# SCH_IRRemote.net
KiCad netlist of a schematic drawn in EasyEDA
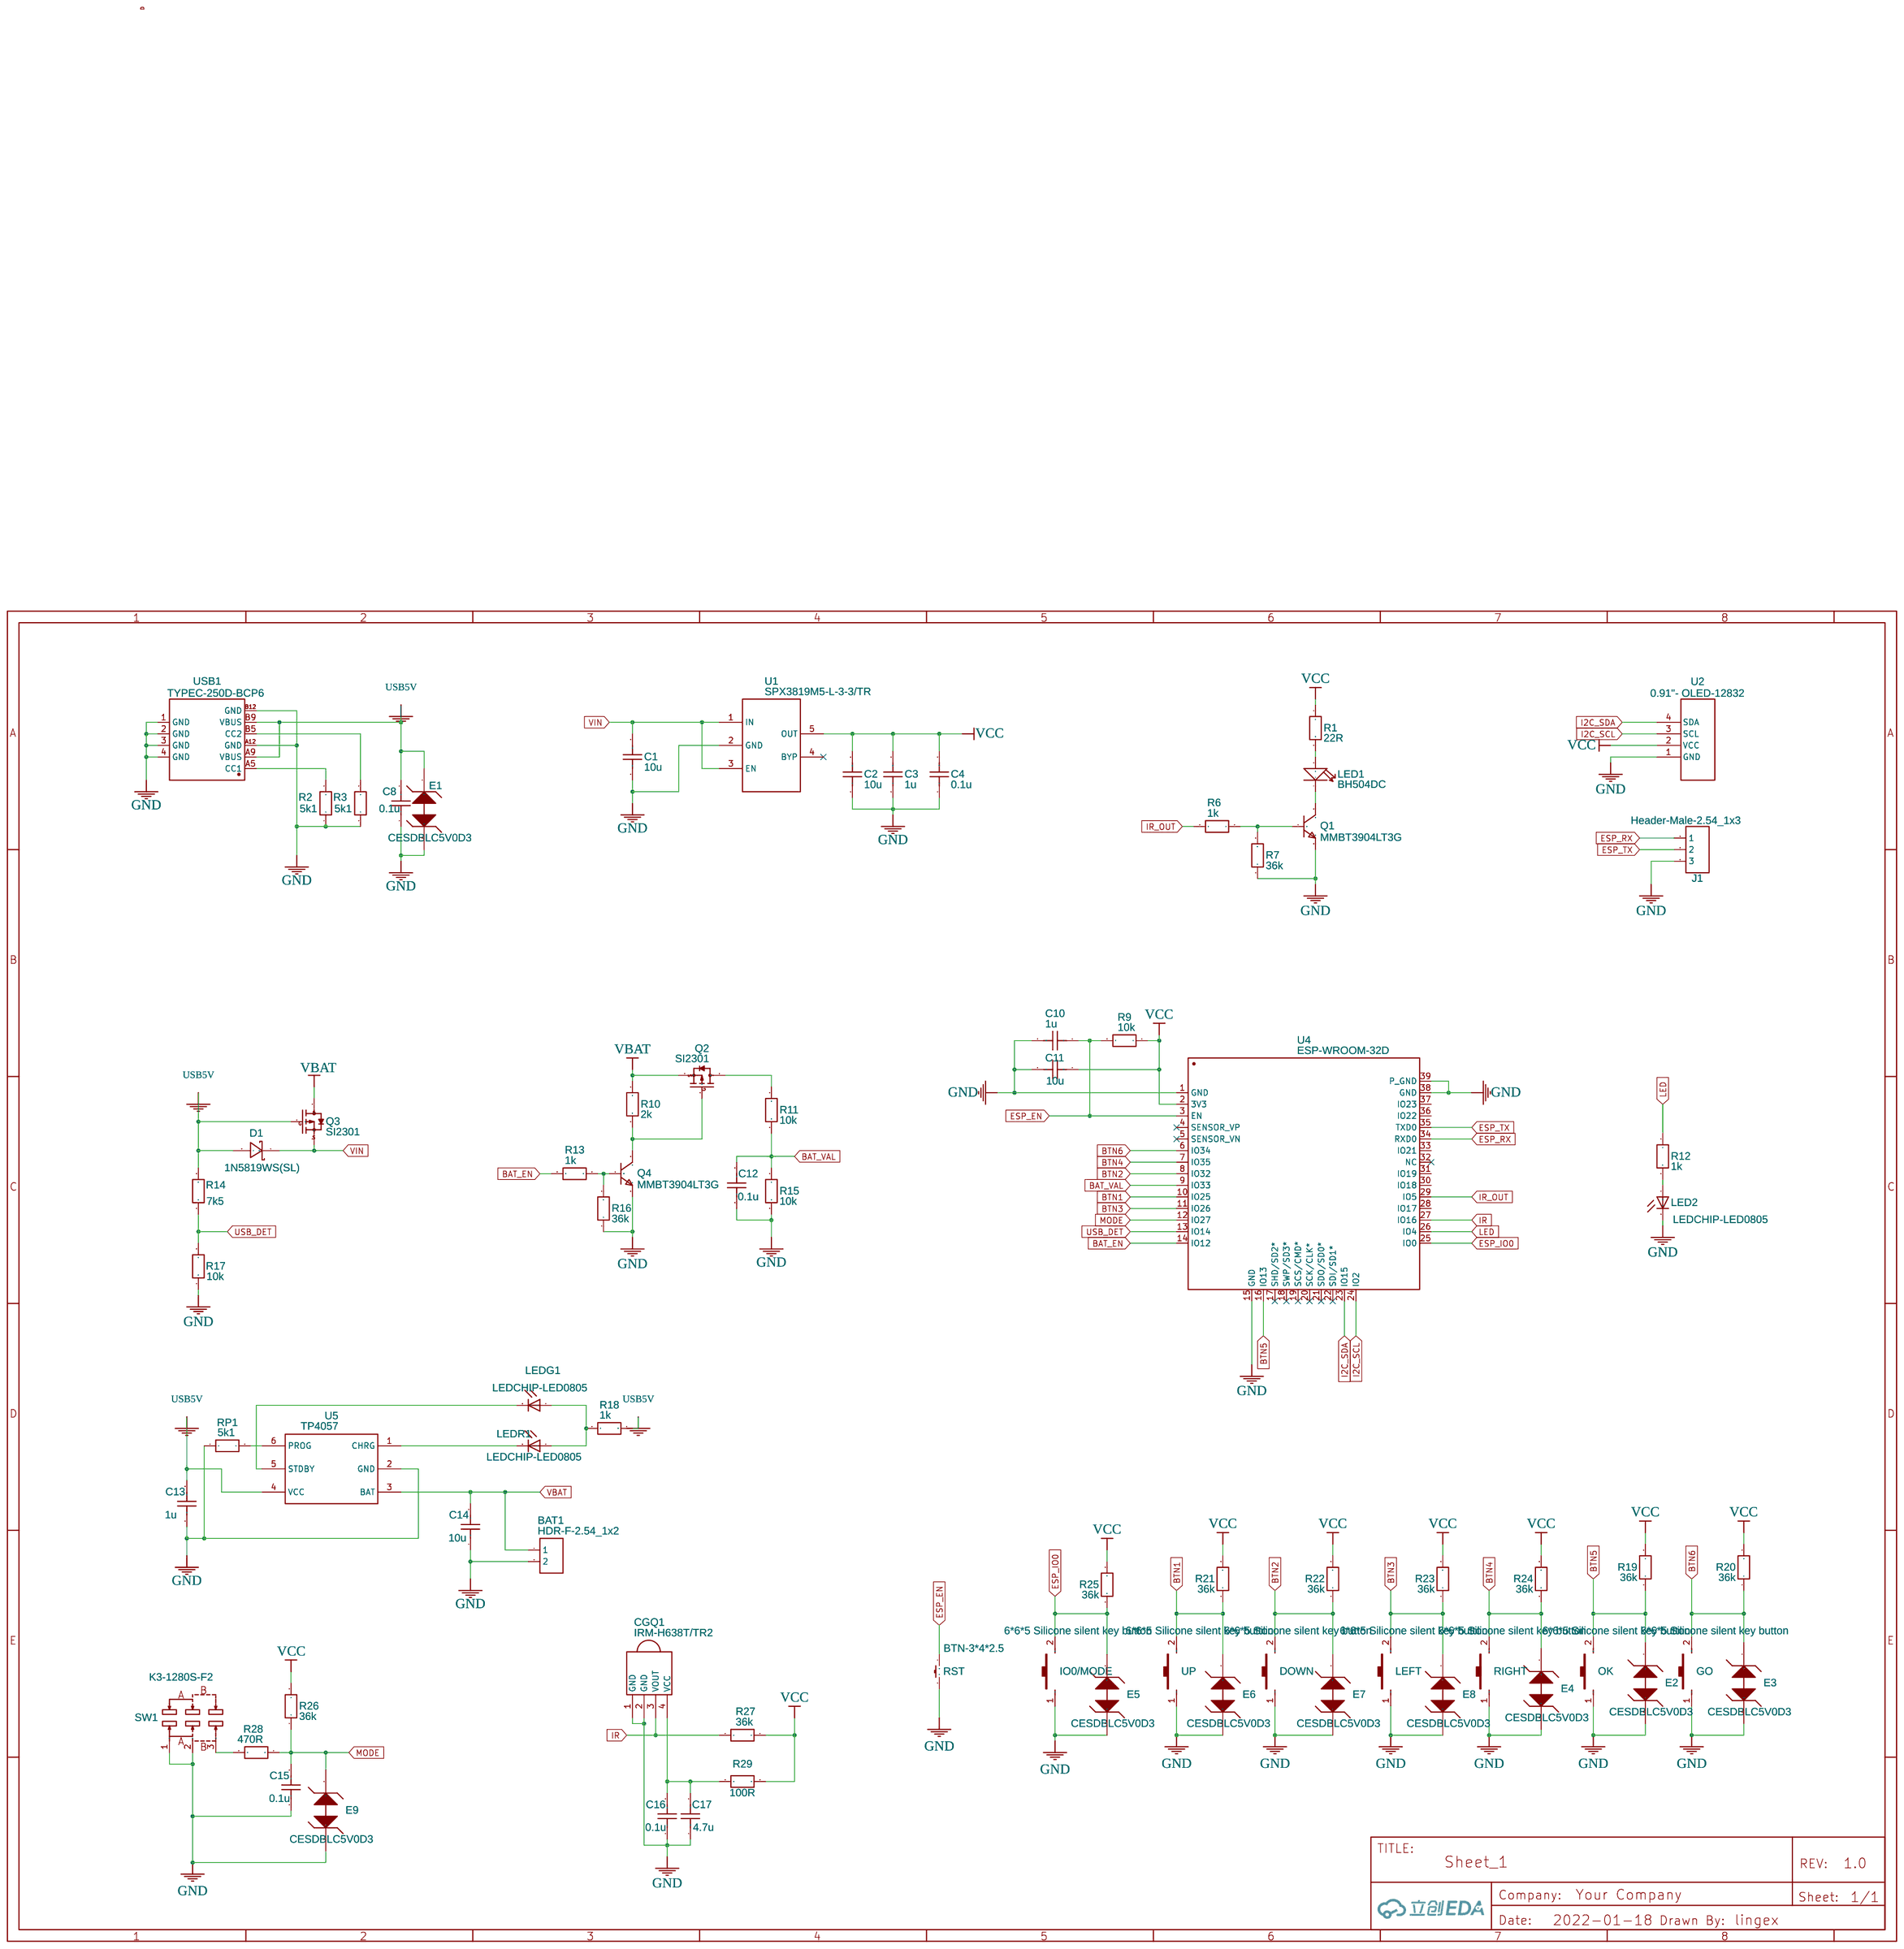
[diagram p0: schematic sheet]

(export (version "E")
  (design (tool "Eeschema 10.0.6"))
  (components
    (comp (ref "BAT1")
      (value "HDR-F-2.54_1x2")
      (fields (field (name "BOM_Supplier Part") "C49661"))
      (libsource (lib "") (part "HDR-F-2.54_1x2"))
    )
    (comp (ref "C1") (value "10u") (libsource (lib "") (part "C_0603_US")))
    (comp (ref "C2") (value "10u") (libsource (lib "") (part "C_0603_US")))
    (comp (ref "C3") (value "1u") (libsource (lib "") (part "C_0603_US")))
    (comp (ref "C4") (value "0.1u") (libsource (lib "") (part "C_0603_US")))
    (comp (ref "C8") (value "0.1u") (libsource (lib "") (part "C_0603_US")))
    (comp (ref "C10") (value "1u") (libsource (lib "") (part "C_0603_US_2")))
    (comp (ref "C11") (value "10u") (libsource (lib "") (part "C_0603_US_2")))
    (comp (ref "C12") (value "0.1u") (libsource (lib "") (part "C_0603_US_1")))
    (comp (ref "C13") (value "1u") (libsource (lib "") (part "C_0603_US")))
    (comp (ref "C14") (value "10u") (libsource (lib "") (part "C_0603_US")))
    (comp (ref "C15") (value "0.1u") (libsource (lib "") (part "C_0603_US")))
    (comp (ref "C16") (value "0.1u") (libsource (lib "") (part "C_0603_US")))
    (comp (ref "C17") (value "4.7u") (libsource (lib "") (part "C_0603_US")))
    (comp (ref "CGQ1")
      (value "IRM-H638T/TR2")
      (fields (field (name "BOM_Supplier Part") "C91447"))
      (libsource (lib "") (part "IRM-H638T/TR2"))
    )
    (comp (ref "D1")
      (value "1N5819WS(SL)")
      (fields (field (name "BOM_Supplier Part") "C489147"))
      (libsource (lib "") (part "1N5819WS(SL)"))
    )
    (comp (ref "DOWN")
      (value "6*6*5 Silicone silent key button")
      (fields (field (name "BOM_Supplier Part") "C61120"))
      (libsource (lib "") (part "6*6*5 Silicone silent key button"))
    )
    (comp (ref "E1")
      (value "CESDBLC5V0D3")
      (fields (field (name "BOM_Supplier Part") "C47346"))
      (libsource (lib "") (part "CESDBLC5V0D3"))
    )
    (comp (ref "E2")
      (value "CESDBLC5V0D3")
      (fields (field (name "BOM_Supplier Part") "C47346"))
      (libsource (lib "") (part "CESDBLC5V0D3"))
    )
    (comp (ref "E3")
      (value "CESDBLC5V0D3")
      (fields (field (name "BOM_Supplier Part") "C47346"))
      (libsource (lib "") (part "CESDBLC5V0D3"))
    )
    (comp (ref "E4")
      (value "CESDBLC5V0D3")
      (fields (field (name "BOM_Supplier Part") "C47346"))
      (libsource (lib "") (part "CESDBLC5V0D3"))
    )
    (comp (ref "E5")
      (value "CESDBLC5V0D3")
      (fields (field (name "BOM_Supplier Part") "C47346"))
      (libsource (lib "") (part "CESDBLC5V0D3"))
    )
    (comp (ref "E6")
      (value "CESDBLC5V0D3")
      (fields (field (name "BOM_Supplier Part") "C47346"))
      (libsource (lib "") (part "CESDBLC5V0D3"))
    )
    (comp (ref "E7")
      (value "CESDBLC5V0D3")
      (fields (field (name "BOM_Supplier Part") "C47346"))
      (libsource (lib "") (part "CESDBLC5V0D3"))
    )
    (comp (ref "E8")
      (value "CESDBLC5V0D3")
      (fields (field (name "BOM_Supplier Part") "C47346"))
      (libsource (lib "") (part "CESDBLC5V0D3"))
    )
    (comp (ref "E9")
      (value "CESDBLC5V0D3")
      (fields (field (name "BOM_Supplier Part") "C47346"))
      (libsource (lib "") (part "CESDBLC5V0D3"))
    )
    (comp (ref "GO")
      (value "6*6*5 Silicone silent key button")
      (fields (field (name "BOM_Supplier Part") "C61120"))
      (libsource (lib "") (part "6*6*5 Silicone silent key button_3"))
    )
    (comp (ref "IO0/MODE")
      (value "6*6*5 Silicone silent key button")
      (fields (field (name "BOM_Supplier Part") "C61120"))
      (libsource (lib "") (part "6*6*5 Silicone silent key button_6"))
    )
    (comp (ref "J1")
      (value "Header-Male-2.54_1x3")
      (fields
        (field (name "BOM_Manufacturer Part") "Header2.54mm 1*3P")
        (field (name "BOM_Supplier Part") "C49257")
      )
      (libsource (lib "") (part "Header-Male-2.54_1x3"))
    )
    (comp (ref "LED1") (value "BH504DC") (libsource (lib "") (part "BH504DC")))
    (comp (ref "LED2") (value "LEDCHIP-LED0805") (libsource (lib "") (part "LEDCHIP-LED0805_2")))
    (comp (ref "LEDG1") (value "LEDCHIP-LED0805") (libsource (lib "") (part "LEDCHIP-LED0805_1")))
    (comp (ref "LEDR1") (value "LEDCHIP-LED0805") (libsource (lib "") (part "LEDCHIP-LED0805")))
    (comp (ref "LEFT")
      (value "6*6*5 Silicone silent key button")
      (fields (field (name "BOM_Supplier Part") "C61120"))
      (libsource (lib "") (part "6*6*5 Silicone silent key button_2"))
    )
    (comp (ref "OK")
      (value "6*6*5 Silicone silent key button")
      (fields (field (name "BOM_Supplier Part") "C61120"))
      (libsource (lib "") (part "6*6*5 Silicone silent key button_5"))
    )
    (comp (ref "Q1")
      (value "MMBT3904LT3G")
      (fields (field (name "BOM_Supplier Part") "C150052"))
      (libsource (lib "") (part "MMBT3904LT3G"))
    )
    (comp (ref "Q2")
      (value "SI2301")
      (fields (field (name "BOM_Supplier Part") "C181086"))
      (libsource (lib "") (part "SI2301_1"))
    )
    (comp (ref "Q3")
      (value "SI2301")
      (fields (field (name "BOM_Supplier Part") "C181086"))
      (libsource (lib "") (part "SI2301"))
    )
    (comp (ref "Q4")
      (value "MMBT3904LT3G")
      (fields (field (name "BOM_Supplier Part") "C150052"))
      (libsource (lib "") (part "MMBT3904LT3G"))
    )
    (comp (ref "R1") (value "22R") (libsource (lib "") (part "R_0603_EU_1")))
    (comp (ref "R2") (value "5k1") (libsource (lib "") (part "R_0603_EU")))
    (comp (ref "R3") (value "5k1") (libsource (lib "") (part "R_0603_EU")))
    (comp (ref "R6") (value "1k") (libsource (lib "") (part "R_0603_EU_2")))
    (comp (ref "R7") (value "36k") (libsource (lib "") (part "R_0603_EU")))
    (comp (ref "R9") (value "10k") (libsource (lib "") (part "R_0603_EU_2")))
    (comp (ref "R10") (value "2k") (libsource (lib "") (part "R_0603_EU_1")))
    (comp (ref "R11") (value "10k") (libsource (lib "") (part "R_0603_EU_1")))
    (comp (ref "R12") (value "1k") (libsource (lib "") (part "R_0603_EU_1")))
    (comp (ref "R13") (value "1k") (libsource (lib "") (part "R_0603_EU_2")))
    (comp (ref "R14") (value "7k5") (libsource (lib "") (part "R_0603_EU")))
    (comp (ref "R15") (value "10k") (libsource (lib "") (part "R_0603_EU_1")))
    (comp (ref "R16") (value "36k") (libsource (lib "") (part "R_0603_EU")))
    (comp (ref "R17") (value "10k") (libsource (lib "") (part "R_0603_EU")))
    (comp (ref "R18") (value "1k") (libsource (lib "") (part "R_0603_EU_3")))
    (comp (ref "R19") (value "36k") (libsource (lib "") (part "R_0603_EU")))
    (comp (ref "R20") (value "36k") (libsource (lib "") (part "R_0603_EU")))
    (comp (ref "R21") (value "36k") (libsource (lib "") (part "R_0603_EU")))
    (comp (ref "R22") (value "36k") (libsource (lib "") (part "R_0603_EU")))
    (comp (ref "R23") (value "36k") (libsource (lib "") (part "R_0603_EU")))
    (comp (ref "R24") (value "36k") (libsource (lib "") (part "R_0603_EU")))
    (comp (ref "R25") (value "36k") (libsource (lib "") (part "R_0603_EU")))
    (comp (ref "R26") (value "36k") (libsource (lib "") (part "R_0603_EU")))
    (comp (ref "R27") (value "36k") (libsource (lib "") (part "R_0603_EU_3")))
    (comp (ref "R28") (value "470R") (libsource (lib "") (part "R_0603_EU_2")))
    (comp (ref "R29") (value "100R") (libsource (lib "") (part "R_0603_EU_3")))
    (comp (ref "RIGHT")
      (value "6*6*5 Silicone silent key button")
      (fields (field (name "BOM_Supplier Part") "C61120"))
      (libsource (lib "") (part "6*6*5 Silicone silent key button_4"))
    )
    (comp (ref "RP1") (value "5k1") (libsource (lib "") (part "R_0603_EU_4")))
    (comp (ref "RST")
      (value "BTN-3*4*2.5")
      (fields
        (field (name "BOM_Manufacturer Part") "UK-B0267-ZT-SP25Y")
        (field (name "BOM_Supplier Part") "C493284")
      )
      (libsource (lib "") (part "3*4*2.5 贴片椭圆白头按钮开关"))
    )
    (comp (ref "SW1")
      (value "K3-1280S-F2")
      (fields (field (name "BOM_Supplier Part") "C92658"))
      (libsource (lib "") (part "K3-1280S-F2"))
    )
    (comp (ref "U1")
      (value "SPX3819M5-L-3-3/TR")
      (fields (field (name "BOM_Supplier Part") "C9055"))
      (libsource (lib "") (part "SPX3819M5-L-3-3/TR"))
    )
    (comp (ref "U2") (value "0.91\"- OLED-12832") (libsource (lib "") (part "0.91{dblquote}- OLED-12832")))
    (comp (ref "U4")
      (value "ESP-WROOM-32D")
      (fields (field (name "BOM_Supplier Part") "C2894836"))
      (libsource (lib "") (part "ESP-WROOM-32D"))
    )
    (comp (ref "U5")
      (value "TP4057")
      (fields (field (name "BOM_Supplier Part") "C12044"))
      (libsource (lib "") (part "TP4057"))
    )
    (comp (ref "UP")
      (value "6*6*5 Silicone silent key button")
      (fields (field (name "BOM_Supplier Part") "C61120"))
      (libsource (lib "") (part "6*6*5 Silicone silent key button_1"))
    )
    (comp (ref "USB1")
      (value "TYPEC-250D-BCP6")
      (fields (field (name "BOM_Supplier Part") "C720626"))
      (libsource (lib "") (part "TYPEC-250D-BCP6"))
    )
  )
  (nets
    (net (code "1") (name "BAT_EN") (class "Default")
      (node (ref "R13") (pin "2") (pinfunction "2_2") (pintype "unspecified"))
      (node (ref "U4") (pin "14") (pinfunction "IO12_14") (pintype "unspecified"))
    )
    (net (code "2") (name "BAT_VAL") (class "Default")
      (node (ref "C12") (pin "1") (pinfunction "1_1") (pintype "unspecified"))
      (node (ref "R11") (pin "2") (pinfunction "2_2") (pintype "unspecified"))
      (node (ref "R15") (pin "1") (pinfunction "1_1") (pintype "unspecified"))
      (node (ref "U4") (pin "9") (pinfunction "IO33_9") (pintype "unspecified"))
    )
    (net (code "3") (name "BTN1") (class "Default")
      (node (ref "E6") (pin "1") (pinfunction "1_1") (pintype "input"))
      (node (ref "R21") (pin "1") (pinfunction "1_1") (pintype "unspecified"))
      (node (ref "U4") (pin "10") (pinfunction "IO25_10") (pintype "unspecified"))
      (node (ref "UP") (pin "2") (pinfunction "2_2") (pintype "input"))
    )
    (net (code "4") (name "BTN2") (class "Default")
      (node (ref "DOWN") (pin "2") (pinfunction "2_2") (pintype "input"))
      (node (ref "E7") (pin "1") (pinfunction "1_1") (pintype "input"))
      (node (ref "R22") (pin "1") (pinfunction "1_1") (pintype "unspecified"))
      (node (ref "U4") (pin "8") (pinfunction "IO32_8") (pintype "unspecified"))
    )
    (net (code "5") (name "BTN3") (class "Default")
      (node (ref "E8") (pin "1") (pinfunction "1_1") (pintype "input"))
      (node (ref "LEFT") (pin "2") (pinfunction "2_2") (pintype "input"))
      (node (ref "R23") (pin "1") (pinfunction "1_1") (pintype "unspecified"))
      (node (ref "U4") (pin "11") (pinfunction "IO26_11") (pintype "unspecified"))
    )
    (net (code "6") (name "BTN4") (class "Default")
      (node (ref "E4") (pin "1") (pinfunction "1_1") (pintype "input"))
      (node (ref "R24") (pin "1") (pinfunction "1_1") (pintype "unspecified"))
      (node (ref "RIGHT") (pin "2") (pinfunction "2_2") (pintype "input"))
      (node (ref "U4") (pin "7") (pinfunction "IO35_7") (pintype "unspecified"))
    )
    (net (code "7") (name "BTN5") (class "Default")
      (node (ref "E2") (pin "1") (pinfunction "1_1") (pintype "input"))
      (node (ref "OK") (pin "2") (pinfunction "2_2") (pintype "input"))
      (node (ref "R19") (pin "1") (pinfunction "1_1") (pintype "unspecified"))
      (node (ref "U4") (pin "16") (pinfunction "IO13_16") (pintype "unspecified"))
    )
    (net (code "8") (name "BTN6") (class "Default")
      (node (ref "E3") (pin "1") (pinfunction "1_1") (pintype "input"))
      (node (ref "GO") (pin "2") (pinfunction "2_2") (pintype "input"))
      (node (ref "R20") (pin "1") (pinfunction "1_1") (pintype "unspecified"))
      (node (ref "U4") (pin "6") (pinfunction "IO34_6") (pintype "unspecified"))
    )
    (net (code "9") (name "ESP_EN") (class "Default")
      (node (ref "C10") (pin "1") (pinfunction "1_1") (pintype "unspecified"))
      (node (ref "R9") (pin "2") (pinfunction "2_2") (pintype "unspecified"))
      (node (ref "RST") (pin "4") (pinfunction "3_4") (pintype "unspecified"))
      (node (ref "U4") (pin "3") (pinfunction "EN_3") (pintype "unspecified"))
    )
    (net (code "10") (name "ESP_IO0") (class "Default")
      (node (ref "E5") (pin "1") (pinfunction "1_1") (pintype "input"))
      (node (ref "IO0/MODE") (pin "2") (pinfunction "2_2") (pintype "input"))
      (node (ref "R25") (pin "1") (pinfunction "1_1") (pintype "unspecified"))
      (node (ref "U4") (pin "25") (pinfunction "IO0_25") (pintype "unspecified"))
    )
    (net (code "11") (name "ESP_RX") (class "Default")
      (node (ref "J1") (pin "1") (pinfunction "1_1") (pintype "input"))
      (node (ref "U4") (pin "34") (pinfunction "RXD0_34") (pintype "unspecified"))
    )
    (net (code "12") (name "ESP_TX") (class "Default")
      (node (ref "J1") (pin "2") (pinfunction "2_2") (pintype "input"))
      (node (ref "U4") (pin "35") (pinfunction "TXD0_35") (pintype "unspecified"))
    )
    (net (code "13") (name "GND") (class "Default")
      (node (ref "BAT1") (pin "2") (pinfunction "2_2") (pintype "input"))
      (node (ref "C1") (pin "1") (pinfunction "1_1") (pintype "unspecified"))
      (node (ref "C10") (pin "2") (pinfunction "2_2") (pintype "unspecified"))
      (node (ref "C11") (pin "2") (pinfunction "2_2") (pintype "unspecified"))
      (node (ref "C12") (pin "2") (pinfunction "2_2") (pintype "unspecified"))
      (node (ref "C13") (pin "1") (pinfunction "1_1") (pintype "unspecified"))
      (node (ref "C14") (pin "1") (pinfunction "1_1") (pintype "unspecified"))
      (node (ref "C15") (pin "1") (pinfunction "1_1") (pintype "unspecified"))
      (node (ref "C16") (pin "1") (pinfunction "1_1") (pintype "unspecified"))
      (node (ref "C17") (pin "1") (pinfunction "1_1") (pintype "unspecified"))
      (node (ref "C2") (pin "1") (pinfunction "1_1") (pintype "unspecified"))
      (node (ref "C3") (pin "1") (pinfunction "1_1") (pintype "unspecified"))
      (node (ref "C4") (pin "1") (pinfunction "1_1") (pintype "unspecified"))
      (node (ref "C8") (pin "1") (pinfunction "1_1") (pintype "unspecified"))
      (node (ref "CGQ1") (pin "1") (pinfunction "GND_1") (pintype "input"))
      (node (ref "CGQ1") (pin "2") (pinfunction "GND_2") (pintype "input"))
      (node (ref "DOWN") (pin "1") (pinfunction "1_1") (pintype "input"))
      (node (ref "E1") (pin "2") (pinfunction "2_2") (pintype "input"))
      (node (ref "E2") (pin "2") (pinfunction "2_2") (pintype "input"))
      (node (ref "E3") (pin "2") (pinfunction "2_2") (pintype "input"))
      (node (ref "E4") (pin "2") (pinfunction "2_2") (pintype "input"))
      (node (ref "E5") (pin "2") (pinfunction "2_2") (pintype "input"))
      (node (ref "E6") (pin "2") (pinfunction "2_2") (pintype "input"))
      (node (ref "E7") (pin "2") (pinfunction "2_2") (pintype "input"))
      (node (ref "E8") (pin "2") (pinfunction "2_2") (pintype "input"))
      (node (ref "E9") (pin "2") (pinfunction "2_2") (pintype "input"))
      (node (ref "GO") (pin "1") (pinfunction "1_1") (pintype "input"))
      (node (ref "IO0/MODE") (pin "1") (pinfunction "1_1") (pintype "input"))
      (node (ref "J1") (pin "3") (pinfunction "3_3") (pintype "input"))
      (node (ref "LED2") (pin "C") (pinfunction "C_C") (pintype "unspecified"))
      (node (ref "LEFT") (pin "1") (pinfunction "1_1") (pintype "input"))
      (node (ref "OK") (pin "1") (pinfunction "1_1") (pintype "input"))
      (node (ref "Q1") (pin "2") (pinfunction "E_2") (pintype "unspecified"))
      (node (ref "Q4") (pin "2") (pinfunction "E_2") (pintype "unspecified"))
      (node (ref "R15") (pin "2") (pinfunction "2_2") (pintype "unspecified"))
      (node (ref "R16") (pin "1") (pinfunction "1_1") (pintype "unspecified"))
      (node (ref "R17") (pin "1") (pinfunction "1_1") (pintype "unspecified"))
      (node (ref "R2") (pin "1") (pinfunction "1_1") (pintype "unspecified"))
      (node (ref "R3") (pin "1") (pinfunction "1_1") (pintype "unspecified"))
      (node (ref "R7") (pin "1") (pinfunction "1_1") (pintype "unspecified"))
      (node (ref "RIGHT") (pin "1") (pinfunction "1_1") (pintype "input"))
      (node (ref "RP1") (pin "1") (pinfunction "1_1") (pintype "unspecified"))
      (node (ref "RST") (pin "1") (pinfunction "1_1") (pintype "unspecified"))
      (node (ref "SW1") (pin "1") (pinfunction "1_1") (pintype "unspecified"))
      (node (ref "SW1") (pin "2") (pinfunction "2_2") (pintype "unspecified"))
      (node (ref "U1") (pin "2") (pinfunction "GND_2") (pintype "unspecified"))
      (node (ref "U2") (pin "1") (pinfunction "GND_1") (pintype "unspecified"))
      (node (ref "U4") (pin "1") (pinfunction "GND_1") (pintype "unspecified"))
      (node (ref "U4") (pin "15") (pinfunction "GND_15") (pintype "unspecified"))
      (node (ref "U4") (pin "38") (pinfunction "GND_38") (pintype "unspecified"))
      (node (ref "U4") (pin "39") (pinfunction "P_GND_39") (pintype "unspecified"))
      (node (ref "U5") (pin "2") (pinfunction "GND_2") (pintype "unspecified"))
      (node (ref "UP") (pin "1") (pinfunction "1_1") (pintype "input"))
      (node (ref "USB1") (pin "1") (pinfunction "GND_1") (pintype "unspecified"))
      (node (ref "USB1") (pin "2") (pinfunction "GND_2") (pintype "unspecified"))
      (node (ref "USB1") (pin "3") (pinfunction "GND_3") (pintype "unspecified"))
      (node (ref "USB1") (pin "4") (pinfunction "GND_4") (pintype "unspecified"))
      (node (ref "USB1") (pin "A12") (pinfunction "GND_A12") (pintype "unspecified"))
      (node (ref "USB1") (pin "B12") (pinfunction "GND_B12") (pintype "unspecified"))
    )
    (net (code "14") (name "I2C_SCL") (class "Default")
      (node (ref "U2") (pin "3") (pinfunction "SCL_3") (pintype "unspecified"))
      (node (ref "U4") (pin "24") (pinfunction "IO2_24") (pintype "unspecified"))
    )
    (net (code "15") (name "I2C_SDA") (class "Default")
      (node (ref "U2") (pin "4") (pinfunction "SDA_4") (pintype "unspecified"))
      (node (ref "U4") (pin "23") (pinfunction "IO15_23") (pintype "unspecified"))
    )
    (net (code "16") (name "IR") (class "Default")
      (node (ref "CGQ1") (pin "3") (pinfunction "VOUT_3") (pintype "input"))
      (node (ref "R27") (pin "1") (pinfunction "1_1") (pintype "unspecified"))
      (node (ref "U4") (pin "27") (pinfunction "IO16_27") (pintype "unspecified"))
    )
    (net (code "17") (name "IR_OUT") (class "Default")
      (node (ref "R6") (pin "2") (pinfunction "2_2") (pintype "unspecified"))
      (node (ref "U4") (pin "29") (pinfunction "IO5_29") (pintype "unspecified"))
    )
    (net (code "18") (name "LED") (class "Default")
      (node (ref "R12") (pin "1") (pinfunction "1_1") (pintype "unspecified"))
      (node (ref "U4") (pin "26") (pinfunction "IO4_26") (pintype "unspecified"))
    )
    (net (code "19") (name "MODE") (class "Default")
      (node (ref "C15") (pin "2") (pinfunction "2_2") (pintype "unspecified"))
      (node (ref "E9") (pin "1") (pinfunction "1_1") (pintype "input"))
      (node (ref "R26") (pin "1") (pinfunction "1_1") (pintype "unspecified"))
      (node (ref "R28") (pin "1") (pinfunction "1_1") (pintype "unspecified"))
      (node (ref "U4") (pin "12") (pinfunction "IO27_12") (pintype "unspecified"))
    )
    (net (code "20") (name "Net-(CGQ1-VCC)") (class "Default")
      (node (ref "C16") (pin "2") (pinfunction "2_2") (pintype "unspecified"))
      (node (ref "C17") (pin "2") (pinfunction "2_2") (pintype "unspecified"))
      (node (ref "CGQ1") (pin "4") (pinfunction "VCC_4") (pintype "input"))
      (node (ref "R29") (pin "1") (pinfunction "1_1") (pintype "unspecified"))
    )
    (net (code "21") (name "Net-(LED1-Pad+)") (class "Default")
      (node (ref "LED1") (pin "+") (pinfunction "+_+") (pintype "unspecified"))
      (node (ref "R1") (pin "2") (pinfunction "2_2") (pintype "unspecified"))
    )
    (net (code "22") (name "Net-(LED2-PadA)") (class "Default")
      (node (ref "LED2") (pin "A") (pinfunction "A_A") (pintype "unspecified"))
      (node (ref "R12") (pin "2") (pinfunction "2_2") (pintype "unspecified"))
    )
    (net (code "23") (name "Net-(LEDG1-PadA)") (class "Default")
      (node (ref "LEDG1") (pin "A") (pinfunction "A_A") (pintype "unspecified"))
      (node (ref "LEDR1") (pin "A") (pinfunction "A_A") (pintype "unspecified"))
      (node (ref "R18") (pin "1") (pinfunction "1_1") (pintype "unspecified"))
    )
    (net (code "24") (name "Net-(Q1-B)") (class "Default")
      (node (ref "Q1") (pin "1") (pinfunction "B_1") (pintype "unspecified"))
      (node (ref "R6") (pin "1") (pinfunction "1_1") (pintype "unspecified"))
      (node (ref "R7") (pin "2") (pinfunction "2_2") (pintype "unspecified"))
    )
    (net (code "25") (name "Net-(Q1-C)") (class "Default")
      (node (ref "LED1") (pin "-") (pinfunction "-_-") (pintype "unspecified"))
      (node (ref "Q1") (pin "3") (pinfunction "C_3") (pintype "unspecified"))
    )
    (net (code "26") (name "Net-(Q2-D)") (class "Default")
      (node (ref "Q2") (pin "3") (pinfunction "D_3") (pintype "unspecified"))
      (node (ref "R11") (pin "1") (pinfunction "1_1") (pintype "unspecified"))
    )
    (net (code "27") (name "Net-(Q2-G)") (class "Default")
      (node (ref "Q2") (pin "1") (pinfunction "G_1") (pintype "unspecified"))
      (node (ref "Q4") (pin "3") (pinfunction "C_3") (pintype "unspecified"))
      (node (ref "R10") (pin "2") (pinfunction "2_2") (pintype "unspecified"))
    )
    (net (code "28") (name "Net-(Q4-B)") (class "Default")
      (node (ref "Q4") (pin "1") (pinfunction "B_1") (pintype "unspecified"))
      (node (ref "R13") (pin "1") (pinfunction "1_1") (pintype "unspecified"))
      (node (ref "R16") (pin "2") (pinfunction "2_2") (pintype "unspecified"))
    )
    (net (code "29") (name "Net-(R28-Pad2)") (class "Default")
      (node (ref "R28") (pin "2") (pinfunction "2_2") (pintype "unspecified"))
      (node (ref "SW1") (pin "3") (pinfunction "3_3") (pintype "unspecified"))
    )
    (net (code "30") (name "Net-(U5-CHRG)") (class "Default")
      (node (ref "LEDR1") (pin "C") (pinfunction "C_C") (pintype "unspecified"))
      (node (ref "U5") (pin "1") (pinfunction "CHRG_1") (pintype "unspecified"))
    )
    (net (code "31") (name "Net-(U5-PROG)") (class "Default")
      (node (ref "RP1") (pin "2") (pinfunction "2_2") (pintype "unspecified"))
      (node (ref "U5") (pin "6") (pinfunction "PROG_6") (pintype "unspecified"))
    )
    (net (code "32") (name "Net-(U5-STDBY)") (class "Default")
      (node (ref "LEDG1") (pin "C") (pinfunction "C_C") (pintype "unspecified"))
      (node (ref "U5") (pin "5") (pinfunction "STDBY_5") (pintype "unspecified"))
    )
    (net (code "33") (name "Net-(USB1-CC1)") (class "Default")
      (node (ref "R2") (pin "2") (pinfunction "2_2") (pintype "unspecified"))
      (node (ref "USB1") (pin "A5") (pinfunction "CC1_A5") (pintype "unspecified"))
    )
    (net (code "34") (name "Net-(USB1-CC2)") (class "Default")
      (node (ref "R3") (pin "2") (pinfunction "2_2") (pintype "unspecified"))
      (node (ref "USB1") (pin "B5") (pinfunction "CC2_B5") (pintype "unspecified"))
    )
    (net (code "35") (name "USB5V") (class "Default")
      (node (ref "C13") (pin "2") (pinfunction "2_2") (pintype "unspecified"))
      (node (ref "C8") (pin "2") (pinfunction "2_2") (pintype "unspecified"))
      (node (ref "D1") (pin "2") (pinfunction "A_2") (pintype "unspecified"))
      (node (ref "E1") (pin "1") (pinfunction "1_1") (pintype "input"))
      (node (ref "Q3") (pin "1") (pinfunction "G_1") (pintype "unspecified"))
      (node (ref "R14") (pin "2") (pinfunction "2_2") (pintype "unspecified"))
      (node (ref "R18") (pin "2") (pinfunction "2_2") (pintype "unspecified"))
      (node (ref "U5") (pin "4") (pinfunction "VCC_4") (pintype "unspecified"))
      (node (ref "USB1") (pin "A9") (pinfunction "VBUS_A9") (pintype "unspecified"))
      (node (ref "USB1") (pin "B9") (pinfunction "VBUS_B9") (pintype "unspecified"))
    )
    (net (code "36") (name "USB_DET") (class "Default")
      (node (ref "R14") (pin "1") (pinfunction "1_1") (pintype "unspecified"))
      (node (ref "R17") (pin "2") (pinfunction "2_2") (pintype "unspecified"))
      (node (ref "U4") (pin "13") (pinfunction "IO14_13") (pintype "unspecified"))
    )
    (net (code "37") (name "VBAT") (class "Default")
      (node (ref "BAT1") (pin "1") (pinfunction "1_1") (pintype "input"))
      (node (ref "C14") (pin "2") (pinfunction "2_2") (pintype "unspecified"))
      (node (ref "Q2") (pin "2") (pinfunction "S_2") (pintype "unspecified"))
      (node (ref "Q3") (pin "3") (pinfunction "D_3") (pintype "unspecified"))
      (node (ref "R10") (pin "1") (pinfunction "1_1") (pintype "unspecified"))
      (node (ref "U5") (pin "3") (pinfunction "BAT_3") (pintype "unspecified"))
    )
    (net (code "38") (name "VCC") (class "Default")
      (node (ref "C11") (pin "1") (pinfunction "1_1") (pintype "unspecified"))
      (node (ref "C2") (pin "2") (pinfunction "2_2") (pintype "unspecified"))
      (node (ref "C3") (pin "2") (pinfunction "2_2") (pintype "unspecified"))
      (node (ref "C4") (pin "2") (pinfunction "2_2") (pintype "unspecified"))
      (node (ref "R1") (pin "1") (pinfunction "1_1") (pintype "unspecified"))
      (node (ref "R19") (pin "2") (pinfunction "2_2") (pintype "unspecified"))
      (node (ref "R20") (pin "2") (pinfunction "2_2") (pintype "unspecified"))
      (node (ref "R21") (pin "2") (pinfunction "2_2") (pintype "unspecified"))
      (node (ref "R22") (pin "2") (pinfunction "2_2") (pintype "unspecified"))
      (node (ref "R23") (pin "2") (pinfunction "2_2") (pintype "unspecified"))
      (node (ref "R24") (pin "2") (pinfunction "2_2") (pintype "unspecified"))
      (node (ref "R25") (pin "2") (pinfunction "2_2") (pintype "unspecified"))
      (node (ref "R26") (pin "2") (pinfunction "2_2") (pintype "unspecified"))
      (node (ref "R27") (pin "2") (pinfunction "2_2") (pintype "unspecified"))
      (node (ref "R29") (pin "2") (pinfunction "2_2") (pintype "unspecified"))
      (node (ref "R9") (pin "1") (pinfunction "1_1") (pintype "unspecified"))
      (node (ref "U1") (pin "5") (pinfunction "OUT_5") (pintype "unspecified"))
      (node (ref "U2") (pin "2") (pinfunction "VCC_2") (pintype "unspecified"))
      (node (ref "U4") (pin "2") (pinfunction "3V3_2") (pintype "unspecified"))
    )
    (net (code "39") (name "VIN") (class "Default")
      (node (ref "C1") (pin "2") (pinfunction "2_2") (pintype "unspecified"))
      (node (ref "D1") (pin "1") (pinfunction "C_1") (pintype "unspecified"))
      (node (ref "Q3") (pin "2") (pinfunction "S_2") (pintype "unspecified"))
      (node (ref "U1") (pin "1") (pinfunction "IN_1") (pintype "unspecified"))
      (node (ref "U1") (pin "3") (pinfunction "EN_3") (pintype "unspecified"))
    )
    (net (code "40") (name "unconnected-(U1-BYP-Pad4)") (class "Default")
      (node (ref "U1") (pin "4") (pinfunction "BYP_4") (pintype "unspecified"))
    )
    (net (code "41") (name "unconnected-(U4-IO17-Pad28)") (class "Default")
      (node (ref "U4") (pin "28") (pinfunction "IO17_28") (pintype "unspecified"))
    )
    (net (code "42") (name "unconnected-(U4-IO18-Pad30)") (class "Default")
      (node (ref "U4") (pin "30") (pinfunction "IO18_30") (pintype "unspecified"))
    )
    (net (code "43") (name "unconnected-(U4-IO19-Pad31)") (class "Default")
      (node (ref "U4") (pin "31") (pinfunction "IO19_31") (pintype "unspecified"))
    )
    (net (code "44") (name "unconnected-(U4-IO21-Pad33)") (class "Default")
      (node (ref "U4") (pin "33") (pinfunction "IO21_33") (pintype "unspecified"))
    )
    (net (code "45") (name "unconnected-(U4-IO22-Pad36)") (class "Default")
      (node (ref "U4") (pin "36") (pinfunction "IO22_36") (pintype "unspecified"))
    )
    (net (code "46") (name "unconnected-(U4-IO23-Pad37)") (class "Default")
      (node (ref "U4") (pin "37") (pinfunction "IO23_37") (pintype "unspecified"))
    )
    (net (code "47") (name "unconnected-(U4-NC-Pad32)") (class "Default")
      (node (ref "U4") (pin "32") (pinfunction "NC_32") (pintype "unspecified+no_connect"))
    )
    (net (code "48") (name "unconnected-(U4-SCK{slash}CLK*-Pad20)") (class "Default")
      (node (ref "U4") (pin "20") (pinfunction "SCK/CLK*_20") (pintype "unspecified"))
    )
    (net (code "49") (name "unconnected-(U4-SCS{slash}CMD*-Pad19)") (class "Default")
      (node (ref "U4") (pin "19") (pinfunction "SCS/CMD*_19") (pintype "unspecified"))
    )
    (net (code "50") (name "unconnected-(U4-SDI{slash}SD1*-Pad22)") (class "Default")
      (node (ref "U4") (pin "22") (pinfunction "SDI/SD1*_22") (pintype "unspecified"))
    )
    (net (code "51") (name "unconnected-(U4-SDO{slash}SD0*-Pad21)") (class "Default")
      (node (ref "U4") (pin "21") (pinfunction "SDO/SD0*_21") (pintype "unspecified"))
    )
    (net (code "52") (name "unconnected-(U4-SENSOR_VN-Pad5)") (class "Default")
      (node (ref "U4") (pin "5") (pinfunction "SENSOR_VN_5") (pintype "unspecified+no_connect"))
    )
    (net (code "53") (name "unconnected-(U4-SENSOR_VP-Pad4)") (class "Default")
      (node (ref "U4") (pin "4") (pinfunction "SENSOR_VP_4") (pintype "unspecified+no_connect"))
    )
    (net (code "54") (name "unconnected-(U4-SHD{slash}SD2*-Pad17)") (class "Default")
      (node (ref "U4") (pin "17") (pinfunction "SHD/SD2*_17") (pintype "unspecified"))
    )
    (net (code "55") (name "unconnected-(U4-SWP{slash}SD3*-Pad18)") (class "Default")
      (node (ref "U4") (pin "18") (pinfunction "SWP/SD3*_18") (pintype "unspecified"))
    )
  )
)
